# main.net
KiCad netlist of a schematic drawn in EAGLE
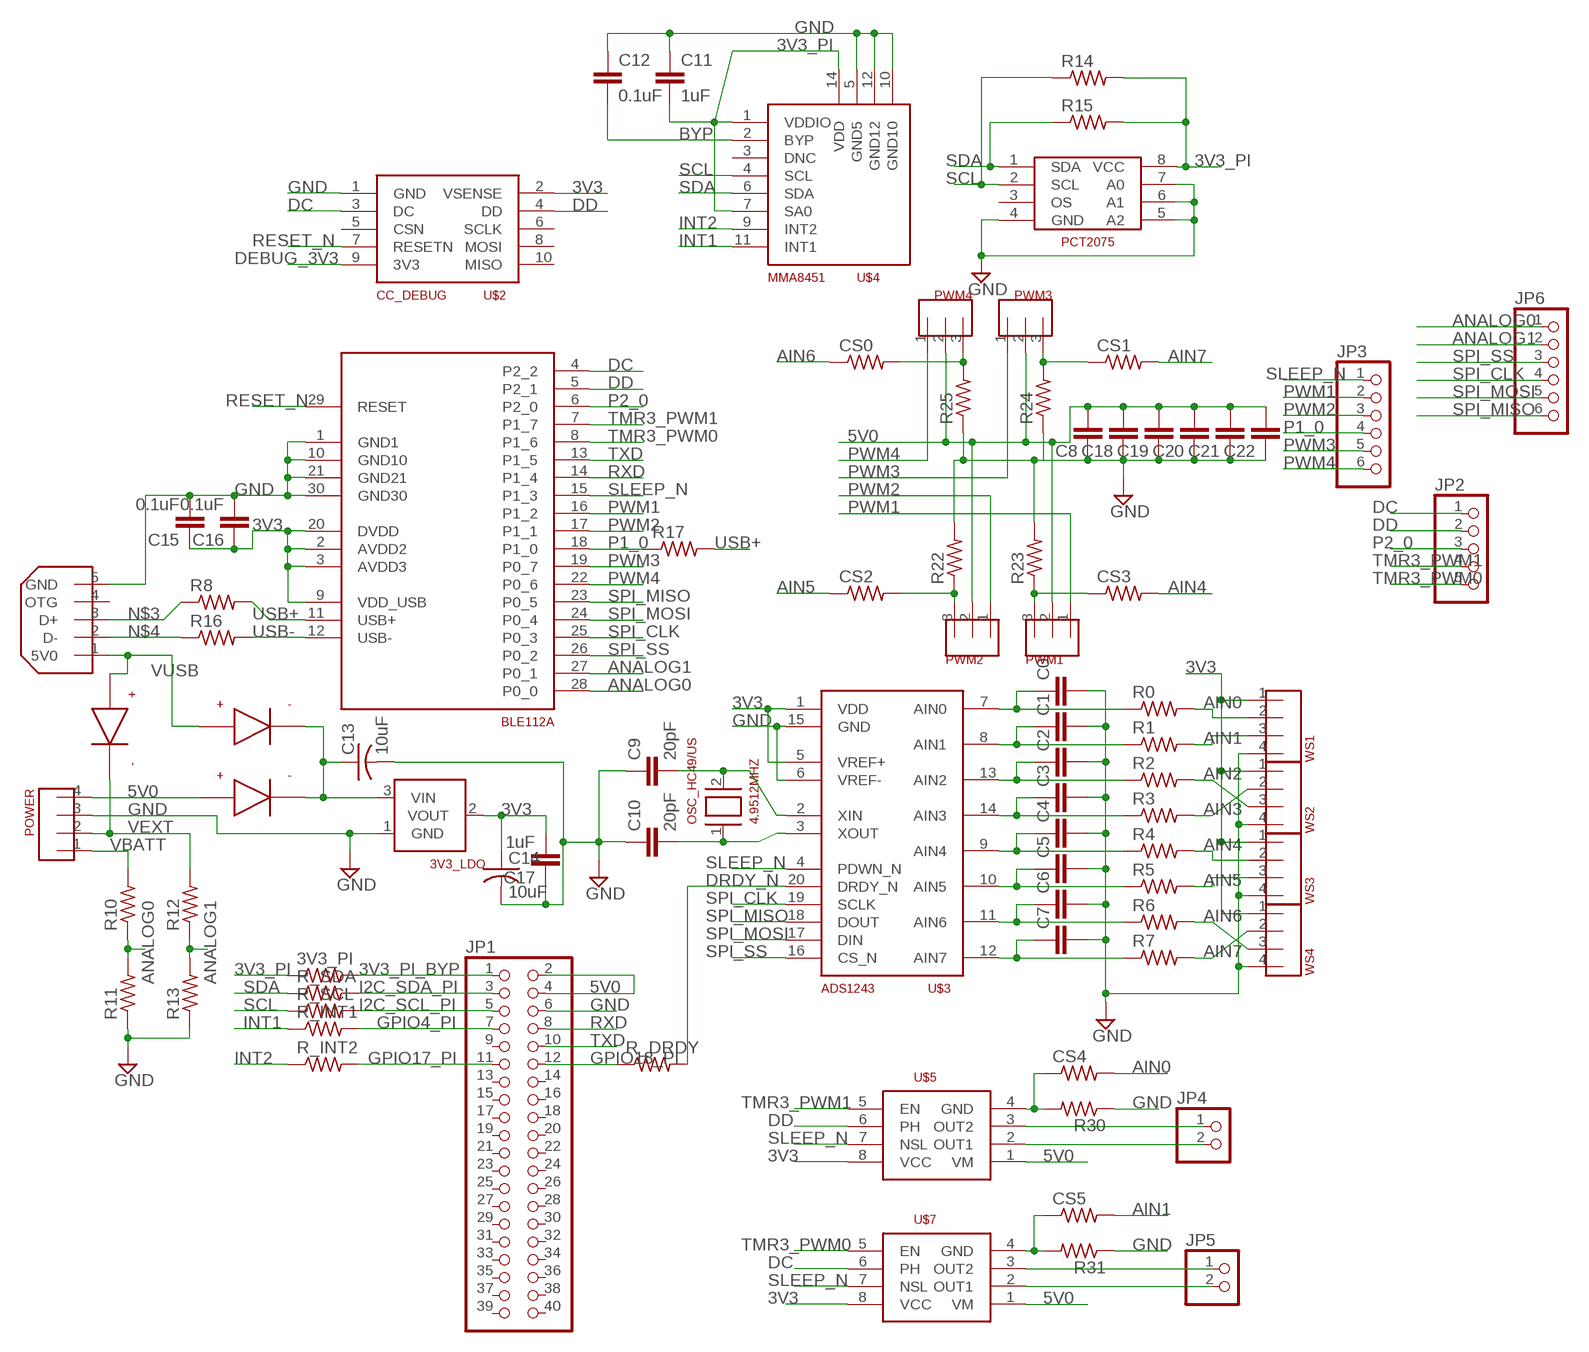
[diagram p0: schematic, sheet 1]

(export (version "E")
  (design (tool "Eeschema 10.0.6"))
  (components
    (comp (ref "3V3_LDO")
      (value "MCP1700")
      (footprint "eagle-import:SOT23")
      (libsource (lib "eagle-import") (part "MCP1700"))
    )
    (comp (ref "3V3_PI")
      (value "R-US_R0603")
      (footprint "eagle-import:R0603")
      (libsource (lib "eagle-import") (part "R-US_R0603"))
    )
    (comp (ref "4.9512MHZ")
      (value "OSC_HC49/US")
      (footprint "eagle-import:HC49UP")
      (libsource (lib "eagle-import") (part "OSC_HC49/US"))
    )
    (comp (ref "BLE112A")
      (value "BLE112A")
      (footprint "eagle-import:BLE112")
      (libsource (lib "eagle-import") (part "BLE112A"))
    )
    (comp (ref "C0")
      (value "C-EUC0603")
      (footprint "eagle-import:C0603")
      (libsource (lib "eagle-import") (part "C-EUC0603"))
    )
    (comp (ref "C1")
      (value "C-EUC0603")
      (footprint "eagle-import:C0603")
      (libsource (lib "eagle-import") (part "C-EUC0603"))
    )
    (comp (ref "C2")
      (value "C-EUC0603")
      (footprint "eagle-import:C0603")
      (libsource (lib "eagle-import") (part "C-EUC0603"))
    )
    (comp (ref "C3")
      (value "C-EUC0603")
      (footprint "eagle-import:C0603")
      (libsource (lib "eagle-import") (part "C-EUC0603"))
    )
    (comp (ref "C4")
      (value "C-EUC0603")
      (footprint "eagle-import:C0603")
      (libsource (lib "eagle-import") (part "C-EUC0603"))
    )
    (comp (ref "C5")
      (value "C-EUC0603")
      (footprint "eagle-import:C0603")
      (libsource (lib "eagle-import") (part "C-EUC0603"))
    )
    (comp (ref "C6")
      (value "C-EUC0603")
      (footprint "eagle-import:C0603")
      (libsource (lib "eagle-import") (part "C-EUC0603"))
    )
    (comp (ref "C7")
      (value "C-EUC0603")
      (footprint "eagle-import:C0603")
      (libsource (lib "eagle-import") (part "C-EUC0603"))
    )
    (comp (ref "C8")
      (value "C-EUC0603")
      (footprint "eagle-import:C0603")
      (libsource (lib "eagle-import") (part "C-EUC0603"))
    )
    (comp (ref "C9")
      (value "20pF")
      (footprint "eagle-import:C0603")
      (libsource (lib "eagle-import") (part "C-EUC0603"))
    )
    (comp (ref "C10")
      (value "20pF")
      (footprint "eagle-import:C0603")
      (libsource (lib "eagle-import") (part "C-EUC0603"))
    )
    (comp (ref "C11")
      (value "1uF")
      (footprint "eagle-import:C0603")
      (libsource (lib "eagle-import") (part "C-EUC0603"))
    )
    (comp (ref "C12")
      (value "0.1uF")
      (footprint "eagle-import:C0603")
      (libsource (lib "eagle-import") (part "C-EUC0603"))
    )
    (comp (ref "C13")
      (value "10uF")
      (footprint "eagle-import:C0805")
      (libsource (lib "eagle-import") (part "C-USC0805"))
    )
    (comp (ref "C14")
      (value "10uF")
      (footprint "eagle-import:C0805")
      (libsource (lib "eagle-import") (part "C-USC0805"))
    )
    (comp (ref "C15")
      (value "0.1uF")
      (footprint "eagle-import:C0603")
      (libsource (lib "eagle-import") (part "C-EUC0603"))
    )
    (comp (ref "C16")
      (value "0.1uF")
      (footprint "eagle-import:C0603")
      (libsource (lib "eagle-import") (part "C-EUC0603"))
    )
    (comp (ref "C17")
      (value "1uF")
      (footprint "eagle-import:C0603")
      (libsource (lib "eagle-import") (part "C-EUC0603"))
    )
    (comp (ref "C18")
      (value "C-EUC0603")
      (footprint "eagle-import:C0603")
      (libsource (lib "eagle-import") (part "C-EUC0603"))
    )
    (comp (ref "C19")
      (value "C-EUC0603")
      (footprint "eagle-import:C0603")
      (libsource (lib "eagle-import") (part "C-EUC0603"))
    )
    (comp (ref "C20")
      (value "C-EUC0603")
      (footprint "eagle-import:C0603")
      (libsource (lib "eagle-import") (part "C-EUC0603"))
    )
    (comp (ref "C21")
      (value "C-EUC0603")
      (footprint "eagle-import:C0603")
      (libsource (lib "eagle-import") (part "C-EUC0603"))
    )
    (comp (ref "C22")
      (value "C-EUC0603")
      (footprint "eagle-import:C0603")
      (libsource (lib "eagle-import") (part "C-EUC0603"))
    )
    (comp (ref "CS0")
      (value "R-US_R0603")
      (footprint "eagle-import:R0603")
      (libsource (lib "eagle-import") (part "R-US_R0603"))
    )
    (comp (ref "CS1")
      (value "R-US_R0603")
      (footprint "eagle-import:R0603")
      (libsource (lib "eagle-import") (part "R-US_R0603"))
    )
    (comp (ref "CS2")
      (value "R-US_R0603")
      (footprint "eagle-import:R0603")
      (libsource (lib "eagle-import") (part "R-US_R0603"))
    )
    (comp (ref "CS3")
      (value "R-US_R0603")
      (footprint "eagle-import:R0603")
      (libsource (lib "eagle-import") (part "R-US_R0603"))
    )
    (comp (ref "CS4")
      (value "R-US_R0603")
      (footprint "eagle-import:R0603")
      (libsource (lib "eagle-import") (part "R-US_R0603"))
    )
    (comp (ref "CS5")
      (value "R-US_R0603")
      (footprint "eagle-import:R0603")
      (libsource (lib "eagle-import") (part "R-US_R0603"))
    )
    (comp (ref "JP1")
      (value "PINHD-2X20")
      (footprint "eagle-import:2X20")
      (libsource (lib "eagle-import") (part "PINHD-2X20"))
    )
    (comp (ref "JP2")
      (value "PINHD-1X5")
      (footprint "eagle-import:1X05")
      (libsource (lib "eagle-import") (part "PINHD-1X5"))
    )
    (comp (ref "JP3")
      (value "PINHD-1X6")
      (footprint "eagle-import:1X06")
      (libsource (lib "eagle-import") (part "PINHD-1X6"))
    )
    (comp (ref "JP4")
      (value "PINHD-1X2")
      (footprint "eagle-import:1X02")
      (libsource (lib "eagle-import") (part "PINHD-1X2"))
    )
    (comp (ref "JP5")
      (value "PINHD-1X2")
      (footprint "eagle-import:1X02")
      (libsource (lib "eagle-import") (part "PINHD-1X2"))
    )
    (comp (ref "JP6")
      (value "PINHD-1X6")
      (footprint "eagle-import:1X06")
      (libsource (lib "eagle-import") (part "PINHD-1X6"))
    )
    (comp (ref "PCT2075")
      (value "PCT2075")
      (footprint "eagle-import:SO-08")
      (libsource (lib "eagle-import") (part "PCT2075"))
    )
    (comp (ref "POWER")
      (value "HDR_SPOX4")
      (footprint "eagle-import:HDR_SPOX4")
      (libsource (lib "eagle-import") (part "HDR_SPOX4"))
    )
    (comp (ref "PWM1")
      (value "HDR_1X3")
      (footprint "eagle-import:HDR_1X3")
      (libsource (lib "eagle-import") (part "HDR_1X3"))
    )
    (comp (ref "PWM2")
      (value "HDR_1X3")
      (footprint "eagle-import:HDR_1X3")
      (libsource (lib "eagle-import") (part "HDR_1X3"))
    )
    (comp (ref "PWM3")
      (value "HDR_1X3")
      (footprint "eagle-import:HDR_1X3")
      (libsource (lib "eagle-import") (part "HDR_1X3"))
    )
    (comp (ref "PWM4")
      (value "HDR_1X3")
      (footprint "eagle-import:HDR_1X3")
      (libsource (lib "eagle-import") (part "HDR_1X3"))
    )
    (comp (ref "R0")
      (value "R-US_R0603")
      (footprint "eagle-import:R0603")
      (libsource (lib "eagle-import") (part "R-US_R0603"))
    )
    (comp (ref "R1")
      (value "R-US_R0603")
      (footprint "eagle-import:R0603")
      (libsource (lib "eagle-import") (part "R-US_R0603"))
    )
    (comp (ref "R2")
      (value "R-US_R0603")
      (footprint "eagle-import:R0603")
      (libsource (lib "eagle-import") (part "R-US_R0603"))
    )
    (comp (ref "R3")
      (value "R-US_R0603")
      (footprint "eagle-import:R0603")
      (libsource (lib "eagle-import") (part "R-US_R0603"))
    )
    (comp (ref "R4")
      (value "R-US_R0603")
      (footprint "eagle-import:R0603")
      (libsource (lib "eagle-import") (part "R-US_R0603"))
    )
    (comp (ref "R5")
      (value "R-US_R0603")
      (footprint "eagle-import:R0603")
      (libsource (lib "eagle-import") (part "R-US_R0603"))
    )
    (comp (ref "R6")
      (value "R-US_R0603")
      (footprint "eagle-import:R0603")
      (libsource (lib "eagle-import") (part "R-US_R0603"))
    )
    (comp (ref "R7")
      (value "R-US_R0603")
      (footprint "eagle-import:R0603")
      (libsource (lib "eagle-import") (part "R-US_R0603"))
    )
    (comp (ref "R8")
      (value "R-US_R0603")
      (footprint "eagle-import:R0603")
      (libsource (lib "eagle-import") (part "R-US_R0603"))
    )
    (comp (ref "R10")
      (value "R-US_R0603")
      (footprint "eagle-import:R0603")
      (libsource (lib "eagle-import") (part "R-US_R0603"))
    )
    (comp (ref "R11")
      (value "R-US_R0603")
      (footprint "eagle-import:R0603")
      (libsource (lib "eagle-import") (part "R-US_R0603"))
    )
    (comp (ref "R12")
      (value "R-US_R0603")
      (footprint "eagle-import:R0603")
      (libsource (lib "eagle-import") (part "R-US_R0603"))
    )
    (comp (ref "R13")
      (value "R-US_R0603")
      (footprint "eagle-import:R0603")
      (libsource (lib "eagle-import") (part "R-US_R0603"))
    )
    (comp (ref "R14")
      (value "R-US_R0603")
      (footprint "eagle-import:R0603")
      (libsource (lib "eagle-import") (part "R-US_R0603"))
    )
    (comp (ref "R15")
      (value "R-US_R0603")
      (footprint "eagle-import:R0603")
      (libsource (lib "eagle-import") (part "R-US_R0603"))
    )
    (comp (ref "R16")
      (value "R-US_R0603")
      (footprint "eagle-import:R0603")
      (libsource (lib "eagle-import") (part "R-US_R0603"))
    )
    (comp (ref "R17")
      (value "R-US_R0603")
      (footprint "eagle-import:R0603")
      (libsource (lib "eagle-import") (part "R-US_R0603"))
    )
    (comp (ref "R22")
      (value "R-US_R1206")
      (footprint "eagle-import:R1206")
      (libsource (lib "eagle-import") (part "resistor_R-US_R1206"))
    )
    (comp (ref "R23")
      (value "R-US_R1206")
      (footprint "eagle-import:R1206")
      (libsource (lib "eagle-import") (part "resistor_R-US_R1206"))
    )
    (comp (ref "R24")
      (value "R-US_R1206")
      (footprint "eagle-import:R1206")
      (libsource (lib "eagle-import") (part "resistor_R-US_R1206"))
    )
    (comp (ref "R25")
      (value "R-US_R1206")
      (footprint "eagle-import:R1206")
      (libsource (lib "eagle-import") (part "resistor_R-US_R1206"))
    )
    (comp (ref "R30")
      (value "R-US_R1206")
      (footprint "eagle-import:R1206")
      (libsource (lib "eagle-import") (part "resistor_R-US_R1206"))
    )
    (comp (ref "R31")
      (value "R-US_R1206")
      (footprint "eagle-import:R1206")
      (libsource (lib "eagle-import") (part "resistor_R-US_R1206"))
    )
    (comp (ref "R_DRDY")
      (value "R-US_R0603")
      (footprint "eagle-import:R0603")
      (libsource (lib "eagle-import") (part "R-US_R0603"))
    )
    (comp (ref "R_INT1")
      (value "R-US_R0603")
      (footprint "eagle-import:R0603")
      (libsource (lib "eagle-import") (part "R-US_R0603"))
    )
    (comp (ref "R_INT2")
      (value "R-US_R0603")
      (footprint "eagle-import:R0603")
      (libsource (lib "eagle-import") (part "R-US_R0603"))
    )
    (comp (ref "R_SCL")
      (value "R-US_R0603")
      (footprint "eagle-import:R0603")
      (libsource (lib "eagle-import") (part "R-US_R0603"))
    )
    (comp (ref "R_SDA")
      (value "R-US_R0603")
      (footprint "eagle-import:R0603")
      (libsource (lib "eagle-import") (part "R-US_R0603"))
    )
    (comp (ref "U$1")
      (value "SCHOTTKEY_DIODE_1206")
      (footprint "eagle-import:DIODE_1206")
      (libsource (lib "eagle-import") (part "SCHOTTKEY_DIODE_1206"))
    )
    (comp (ref "U$2")
      (value "CC_DEBUG")
      (footprint "eagle-import:HDR_2X5_127MM")
      (libsource (lib "eagle-import") (part "CC_DEBUG"))
    )
    (comp (ref "U$3")
      (value "ADS1243")
      (footprint "eagle-import:TSSOP20")
      (libsource (lib "eagle-import") (part "ADS1243"))
    )
    (comp (ref "U$4")
      (value "MMA8451")
      (footprint "eagle-import:QFN16_3X3")
      (libsource (lib "eagle-import") (part "MMA8451"))
    )
    (comp (ref "U$5")
      (value "DRV8838")
      (footprint "eagle-import:WSON-8-PAD")
      (libsource (lib "eagle-import") (part "DRV8838"))
    )
    (comp (ref "U$6")
      (value "MICRO_USB")
      (footprint "eagle-import:MICRO_USB")
      (libsource (lib "eagle-import") (part "MICRO_USB"))
    )
    (comp (ref "U$7")
      (value "DRV8838")
      (footprint "eagle-import:WSON-8-PAD")
      (libsource (lib "eagle-import") (part "DRV8838"))
    )
    (comp (ref "U$11")
      (value "SCHOTTKEY_DIODE_1206")
      (footprint "eagle-import:DIODE_1206")
      (libsource (lib "eagle-import") (part "SCHOTTKEY_DIODE_1206"))
    )
    (comp (ref "U$12")
      (value "SCHOTTKEY_DIODE_1206")
      (footprint "eagle-import:DIODE_1206")
      (libsource (lib "eagle-import") (part "SCHOTTKEY_DIODE_1206"))
    )
    (comp (ref "WS1")
      (value "HDR_1X4")
      (footprint "eagle-import:HDR_1X4")
      (libsource (lib "eagle-import") (part "HDR_1X4"))
    )
    (comp (ref "WS2")
      (value "HDR_1X4")
      (footprint "eagle-import:HDR_1X4")
      (libsource (lib "eagle-import") (part "HDR_1X4"))
    )
    (comp (ref "WS3")
      (value "HDR_1X4")
      (footprint "eagle-import:HDR_1X4")
      (libsource (lib "eagle-import") (part "HDR_1X4"))
    )
    (comp (ref "WS4")
      (value "HDR_1X4")
      (footprint "eagle-import:HDR_1X4")
      (libsource (lib "eagle-import") (part "HDR_1X4"))
    )
  )
  (nets
    (net (code "1") (name "/3V3") (class "Default")
      (node (ref "3V3_LDO") (pin "2") (pinfunction "VOUT_2") (pintype "bidirectional"))
      (node (ref "BLE112A") (pin "2") (pinfunction "AVDD2_2") (pintype "bidirectional"))
      (node (ref "BLE112A") (pin "20") (pinfunction "DVDD_20") (pintype "bidirectional"))
      (node (ref "BLE112A") (pin "3") (pinfunction "AVDD3_3") (pintype "bidirectional"))
      (node (ref "BLE112A") (pin "9") (pinfunction "VDD_USB_9") (pintype "bidirectional"))
      (node (ref "C14") (pin "1") (pinfunction "1_1") (pintype "passive"))
      (node (ref "C15") (pin "1") (pinfunction "1_1") (pintype "passive"))
      (node (ref "C16") (pin "1") (pinfunction "1_1") (pintype "passive"))
      (node (ref "C17") (pin "2") (pinfunction "2_2") (pintype "passive"))
      (node (ref "U$2") (pin "2") (pinfunction "VSENSE_2") (pintype "bidirectional"))
      (node (ref "U$3") (pin "1") (pinfunction "VDD_1") (pintype "bidirectional"))
      (node (ref "U$3") (pin "5") (pinfunction "VREF+_5") (pintype "bidirectional"))
      (node (ref "U$5") (pin "8") (pinfunction "VCC_8") (pintype "bidirectional"))
      (node (ref "U$7") (pin "8") (pinfunction "VCC_8") (pintype "bidirectional"))
      (node (ref "WS1") (pin "1") (pinfunction "1_1") (pintype "bidirectional"))
      (node (ref "WS2") (pin "1") (pinfunction "1_1") (pintype "bidirectional"))
      (node (ref "WS3") (pin "1") (pinfunction "1_1") (pintype "bidirectional"))
      (node (ref "WS4") (pin "1") (pinfunction "1_1") (pintype "bidirectional"))
    )
    (net (code "2") (name "/3V3_PI") (class "Default")
      (node (ref "3V3_PI") (pin "1") (pinfunction "1_1") (pintype "passive"))
      (node (ref "C11") (pin "2") (pinfunction "2_2") (pintype "passive"))
      (node (ref "PCT2075") (pin "8") (pinfunction "VCC_8") (pintype "bidirectional"))
      (node (ref "R14") (pin "2") (pinfunction "2_2") (pintype "passive"))
      (node (ref "R15") (pin "2") (pinfunction "2_2") (pintype "passive"))
      (node (ref "U$4") (pin "1") (pinfunction "VDDIO_1") (pintype "bidirectional"))
      (node (ref "U$4") (pin "14") (pinfunction "VDD_14") (pintype "bidirectional"))
      (node (ref "U$4") (pin "7") (pinfunction "SA0_7") (pintype "bidirectional"))
    )
    (net (code "3") (name "/3V3_PI_BYP") (class "Default")
      (node (ref "3V3_PI") (pin "2") (pinfunction "2_2") (pintype "passive"))
      (node (ref "JP1") (pin "1") (pinfunction "1_1") (pintype "passive"))
    )
    (net (code "4") (name "/5V0") (class "Default")
      (node (ref "C18") (pin "2") (pinfunction "2_2") (pintype "passive"))
      (node (ref "C19") (pin "2") (pinfunction "2_2") (pintype "passive"))
      (node (ref "C20") (pin "2") (pinfunction "2_2") (pintype "passive"))
      (node (ref "C21") (pin "2") (pinfunction "2_2") (pintype "passive"))
      (node (ref "C22") (pin "2") (pinfunction "2_2") (pintype "passive"))
      (node (ref "C8") (pin "2") (pinfunction "2_2") (pintype "passive"))
      (node (ref "JP1") (pin "2") (pinfunction "2_2") (pintype "passive"))
      (node (ref "JP1") (pin "4") (pinfunction "4_4") (pintype "passive"))
      (node (ref "POWER") (pin "4") (pinfunction "4_4") (pintype "bidirectional"))
      (node (ref "PWM1") (pin "2") (pinfunction "2_2") (pintype "bidirectional"))
      (node (ref "PWM2") (pin "2") (pinfunction "2_2") (pintype "bidirectional"))
      (node (ref "PWM3") (pin "2") (pinfunction "2_2") (pintype "bidirectional"))
      (node (ref "PWM4") (pin "2") (pinfunction "2_2") (pintype "bidirectional"))
      (node (ref "U$12") (pin "CATHODE+") (pinfunction "CATHODE+_CATHODE+") (pintype "bidirectional"))
      (node (ref "U$5") (pin "1") (pinfunction "VM_1") (pintype "bidirectional"))
      (node (ref "U$7") (pin "1") (pinfunction "VM_1") (pintype "bidirectional"))
    )
    (net (code "5") (name "/AIN0") (class "Default")
      (node (ref "CS4") (pin "2") (pinfunction "2_2") (pintype "passive"))
      (node (ref "R0") (pin "2") (pinfunction "2_2") (pintype "passive"))
      (node (ref "WS1") (pin "2") (pinfunction "2_2") (pintype "bidirectional"))
    )
    (net (code "6") (name "/AIN1") (class "Default")
      (node (ref "CS5") (pin "2") (pinfunction "2_2") (pintype "passive"))
      (node (ref "R1") (pin "2") (pinfunction "2_2") (pintype "passive"))
      (node (ref "WS1") (pin "3") (pinfunction "3_3") (pintype "bidirectional"))
    )
    (net (code "7") (name "/AIN2") (class "Default")
      (node (ref "R2") (pin "2") (pinfunction "2_2") (pintype "passive"))
      (node (ref "WS2") (pin "3") (pinfunction "3_3") (pintype "bidirectional"))
    )
    (net (code "8") (name "/AIN3") (class "Default")
      (node (ref "R3") (pin "2") (pinfunction "2_2") (pintype "passive"))
      (node (ref "WS2") (pin "2") (pinfunction "2_2") (pintype "bidirectional"))
    )
    (net (code "9") (name "/AIN4") (class "Default")
      (node (ref "CS3") (pin "2") (pinfunction "2_2") (pintype "passive"))
      (node (ref "R4") (pin "2") (pinfunction "2_2") (pintype "passive"))
      (node (ref "WS3") (pin "2") (pinfunction "2_2") (pintype "bidirectional"))
    )
    (net (code "10") (name "/AIN5") (class "Default")
      (node (ref "CS2") (pin "1") (pinfunction "1_1") (pintype "passive"))
      (node (ref "R5") (pin "2") (pinfunction "2_2") (pintype "passive"))
      (node (ref "WS3") (pin "3") (pinfunction "3_3") (pintype "bidirectional"))
    )
    (net (code "11") (name "/AIN6") (class "Default")
      (node (ref "CS0") (pin "1") (pinfunction "1_1") (pintype "passive"))
      (node (ref "R6") (pin "2") (pinfunction "2_2") (pintype "passive"))
      (node (ref "WS4") (pin "3") (pinfunction "3_3") (pintype "bidirectional"))
    )
    (net (code "12") (name "/AIN7") (class "Default")
      (node (ref "CS1") (pin "2") (pinfunction "2_2") (pintype "passive"))
      (node (ref "R7") (pin "2") (pinfunction "2_2") (pintype "passive"))
      (node (ref "WS4") (pin "2") (pinfunction "2_2") (pintype "bidirectional"))
    )
    (net (code "13") (name "/ANALOG0") (class "Default")
      (node (ref "BLE112A") (pin "28") (pinfunction "P0_0_28") (pintype "bidirectional"))
      (node (ref "JP6") (pin "1") (pinfunction "1_1") (pintype "passive"))
      (node (ref "R10") (pin "1") (pinfunction "1_1") (pintype "passive"))
      (node (ref "R11") (pin "2") (pinfunction "2_2") (pintype "passive"))
    )
    (net (code "14") (name "/ANALOG1") (class "Default")
      (node (ref "BLE112A") (pin "27") (pinfunction "P0_1_27") (pintype "bidirectional"))
      (node (ref "JP6") (pin "2") (pinfunction "2_2") (pintype "passive"))
      (node (ref "R12") (pin "1") (pinfunction "1_1") (pintype "passive"))
      (node (ref "R13") (pin "2") (pinfunction "2_2") (pintype "passive"))
    )
    (net (code "15") (name "/BYP") (class "Default")
      (node (ref "C12") (pin "2") (pinfunction "2_2") (pintype "passive"))
      (node (ref "U$4") (pin "2") (pinfunction "BYP_2") (pintype "bidirectional"))
    )
    (net (code "16") (name "/DC") (class "Default")
      (node (ref "BLE112A") (pin "4") (pinfunction "P2_2_4") (pintype "bidirectional"))
      (node (ref "JP2") (pin "1") (pinfunction "1_1") (pintype "passive"))
      (node (ref "U$2") (pin "3") (pinfunction "DC_3") (pintype "bidirectional"))
      (node (ref "U$7") (pin "6") (pinfunction "PH_6") (pintype "bidirectional"))
    )
    (net (code "17") (name "/DD") (class "Default")
      (node (ref "BLE112A") (pin "5") (pinfunction "P2_1_5") (pintype "bidirectional"))
      (node (ref "JP2") (pin "2") (pinfunction "2_2") (pintype "passive"))
      (node (ref "U$2") (pin "4") (pinfunction "DD_4") (pintype "bidirectional"))
      (node (ref "U$5") (pin "6") (pinfunction "PH_6") (pintype "bidirectional"))
    )
    (net (code "18") (name "/DEBUG_3V3") (class "Default")
      (node (ref "U$2") (pin "9") (pinfunction "3V3_9") (pintype "bidirectional"))
    )
    (net (code "19") (name "/DRDY_N") (class "Default")
      (node (ref "R_DRDY") (pin "2") (pinfunction "2_2") (pintype "passive"))
      (node (ref "U$3") (pin "20") (pinfunction "DRDY_N_20") (pintype "bidirectional"))
    )
    (net (code "20") (name "/GPIO4_PI") (class "Default")
      (node (ref "JP1") (pin "7") (pinfunction "7_7") (pintype "passive"))
      (node (ref "R_INT1") (pin "2") (pinfunction "2_2") (pintype "passive"))
    )
    (net (code "21") (name "/GPIO17_PI") (class "Default")
      (node (ref "JP1") (pin "11") (pinfunction "11_11") (pintype "passive"))
      (node (ref "R_INT2") (pin "2") (pinfunction "2_2") (pintype "passive"))
    )
    (net (code "22") (name "/GPIO18_PI") (class "Default")
      (node (ref "JP1") (pin "12") (pinfunction "12_12") (pintype "passive"))
      (node (ref "R_DRDY") (pin "1") (pinfunction "1_1") (pintype "passive"))
    )
    (net (code "23") (name "/I2C_SCL_PI") (class "Default")
      (node (ref "JP1") (pin "5") (pinfunction "5_5") (pintype "passive"))
      (node (ref "R_SCL") (pin "2") (pinfunction "2_2") (pintype "passive"))
    )
    (net (code "24") (name "/I2C_SDA_PI") (class "Default")
      (node (ref "JP1") (pin "3") (pinfunction "3_3") (pintype "passive"))
      (node (ref "R_SDA") (pin "2") (pinfunction "2_2") (pintype "passive"))
    )
    (net (code "25") (name "/INT1") (class "Default")
      (node (ref "R_INT1") (pin "1") (pinfunction "1_1") (pintype "passive"))
      (node (ref "U$4") (pin "11") (pinfunction "INT1_11") (pintype "bidirectional"))
    )
    (net (code "26") (name "/INT2") (class "Default")
      (node (ref "R_INT2") (pin "1") (pinfunction "1_1") (pintype "passive"))
      (node (ref "U$4") (pin "9") (pinfunction "INT2_9") (pintype "bidirectional"))
    )
    (net (code "27") (name "/N$3") (class "Default")
      (node (ref "R8") (pin "1") (pinfunction "1_1") (pintype "passive"))
      (node (ref "U$6") (pin "3") (pinfunction "D+_3") (pintype "bidirectional"))
    )
    (net (code "28") (name "/N$4") (class "Default")
      (node (ref "R16") (pin "1") (pinfunction "1_1") (pintype "passive"))
      (node (ref "U$6") (pin "2") (pinfunction "D-_2") (pintype "bidirectional"))
    )
    (net (code "29") (name "/P1_0") (class "Default")
      (node (ref "BLE112A") (pin "18") (pinfunction "P1_0_18") (pintype "bidirectional"))
      (node (ref "JP3") (pin "4") (pinfunction "4_4") (pintype "passive"))
      (node (ref "R17") (pin "1") (pinfunction "1_1") (pintype "passive"))
    )
    (net (code "30") (name "/P2_0") (class "Default")
      (node (ref "BLE112A") (pin "6") (pinfunction "P2_0_6") (pintype "bidirectional"))
      (node (ref "JP2") (pin "3") (pinfunction "3_3") (pintype "passive"))
    )
    (net (code "31") (name "/PWM1") (class "Default")
      (node (ref "BLE112A") (pin "16") (pinfunction "P1_2_16") (pintype "bidirectional"))
      (node (ref "JP3") (pin "2") (pinfunction "2_2") (pintype "passive"))
      (node (ref "PWM1") (pin "1") (pinfunction "1_1") (pintype "bidirectional"))
    )
    (net (code "32") (name "/PWM2") (class "Default")
      (node (ref "BLE112A") (pin "17") (pinfunction "P1_1_17") (pintype "bidirectional"))
      (node (ref "JP3") (pin "3") (pinfunction "3_3") (pintype "passive"))
      (node (ref "PWM2") (pin "1") (pinfunction "1_1") (pintype "bidirectional"))
    )
    (net (code "33") (name "/PWM3") (class "Default")
      (node (ref "BLE112A") (pin "19") (pinfunction "P0_7_19") (pintype "bidirectional"))
      (node (ref "JP3") (pin "5") (pinfunction "5_5") (pintype "passive"))
      (node (ref "PWM3") (pin "1") (pinfunction "1_1") (pintype "bidirectional"))
    )
    (net (code "34") (name "/PWM4") (class "Default")
      (node (ref "BLE112A") (pin "22") (pinfunction "P0_6_22") (pintype "bidirectional"))
      (node (ref "JP3") (pin "6") (pinfunction "6_6") (pintype "passive"))
      (node (ref "PWM4") (pin "1") (pinfunction "1_1") (pintype "bidirectional"))
    )
    (net (code "35") (name "/RESET_N") (class "Default")
      (node (ref "BLE112A") (pin "29") (pinfunction "RESET_29") (pintype "bidirectional"))
      (node (ref "U$2") (pin "7") (pinfunction "RESETN_7") (pintype "bidirectional"))
    )
    (net (code "36") (name "/RXD") (class "Default")
      (node (ref "BLE112A") (pin "14") (pinfunction "P1_4_14") (pintype "bidirectional"))
      (node (ref "JP1") (pin "8") (pinfunction "8_8") (pintype "passive"))
    )
    (net (code "37") (name "/SCL") (class "Default")
      (node (ref "PCT2075") (pin "2") (pinfunction "SCL_2") (pintype "bidirectional"))
      (node (ref "R14") (pin "1") (pinfunction "1_1") (pintype "passive"))
      (node (ref "R_SCL") (pin "1") (pinfunction "1_1") (pintype "passive"))
      (node (ref "U$4") (pin "4") (pinfunction "SCL_4") (pintype "bidirectional"))
    )
    (net (code "38") (name "/SDA") (class "Default")
      (node (ref "PCT2075") (pin "1") (pinfunction "SDA_1") (pintype "bidirectional"))
      (node (ref "R15") (pin "1") (pinfunction "1_1") (pintype "passive"))
      (node (ref "R_SDA") (pin "1") (pinfunction "1_1") (pintype "passive"))
      (node (ref "U$4") (pin "6") (pinfunction "SDA_6") (pintype "bidirectional"))
    )
    (net (code "39") (name "/SLEEP_N") (class "Default")
      (node (ref "BLE112A") (pin "15") (pinfunction "P1_3_15") (pintype "bidirectional"))
      (node (ref "JP3") (pin "1") (pinfunction "1_1") (pintype "passive"))
      (node (ref "U$3") (pin "4") (pinfunction "PDWN_N_4") (pintype "bidirectional"))
      (node (ref "U$5") (pin "7") (pinfunction "NSL_7") (pintype "bidirectional"))
      (node (ref "U$7") (pin "7") (pinfunction "NSL_7") (pintype "bidirectional"))
    )
    (net (code "40") (name "/SPI_CLK") (class "Default")
      (node (ref "BLE112A") (pin "25") (pinfunction "P0_3_25") (pintype "bidirectional"))
      (node (ref "JP6") (pin "4") (pinfunction "4_4") (pintype "passive"))
      (node (ref "U$3") (pin "19") (pinfunction "SCLK_19") (pintype "bidirectional"))
    )
    (net (code "41") (name "/SPI_MISO") (class "Default")
      (node (ref "BLE112A") (pin "23") (pinfunction "P0_5_23") (pintype "bidirectional"))
      (node (ref "JP6") (pin "6") (pinfunction "6_6") (pintype "passive"))
      (node (ref "U$3") (pin "18") (pinfunction "DOUT_18") (pintype "bidirectional"))
    )
    (net (code "42") (name "/SPI_MOSI") (class "Default")
      (node (ref "BLE112A") (pin "24") (pinfunction "P0_4_24") (pintype "bidirectional"))
      (node (ref "JP6") (pin "5") (pinfunction "5_5") (pintype "passive"))
      (node (ref "U$3") (pin "17") (pinfunction "DIN_17") (pintype "bidirectional"))
    )
    (net (code "43") (name "/SPI_SS") (class "Default")
      (node (ref "BLE112A") (pin "26") (pinfunction "P0_2_26") (pintype "bidirectional"))
      (node (ref "JP6") (pin "3") (pinfunction "3_3") (pintype "passive"))
      (node (ref "U$3") (pin "16") (pinfunction "CS_N_16") (pintype "bidirectional"))
    )
    (net (code "44") (name "/TMR3_PWM0") (class "Default")
      (node (ref "BLE112A") (pin "8") (pinfunction "P1_6_8") (pintype "bidirectional"))
      (node (ref "JP2") (pin "5") (pinfunction "5_5") (pintype "passive"))
      (node (ref "U$7") (pin "5") (pinfunction "EN_5") (pintype "bidirectional"))
    )
    (net (code "45") (name "/TMR3_PWM1") (class "Default")
      (node (ref "BLE112A") (pin "7") (pinfunction "P1_7_7") (pintype "bidirectional"))
      (node (ref "JP2") (pin "4") (pinfunction "4_4") (pintype "passive"))
      (node (ref "U$5") (pin "5") (pinfunction "EN_5") (pintype "bidirectional"))
    )
    (net (code "46") (name "/TXD") (class "Default")
      (node (ref "BLE112A") (pin "13") (pinfunction "P1_5_13") (pintype "bidirectional"))
      (node (ref "JP1") (pin "10") (pinfunction "10_10") (pintype "passive"))
    )
    (net (code "47") (name "/USB+") (class "Default")
      (node (ref "BLE112A") (pin "11") (pinfunction "USB+_11") (pintype "bidirectional"))
      (node (ref "R17") (pin "2") (pinfunction "2_2") (pintype "passive"))
      (node (ref "R8") (pin "2") (pinfunction "2_2") (pintype "passive"))
    )
    (net (code "48") (name "/USB-") (class "Default")
      (node (ref "BLE112A") (pin "12") (pinfunction "USB-_12") (pintype "bidirectional"))
      (node (ref "R16") (pin "2") (pinfunction "2_2") (pintype "passive"))
    )
    (net (code "49") (name "/VBATT") (class "Default")
      (node (ref "POWER") (pin "1") (pinfunction "1_1") (pintype "bidirectional"))
      (node (ref "R10") (pin "2") (pinfunction "2_2") (pintype "passive"))
    )
    (net (code "50") (name "/VEXT") (class "Default")
      (node (ref "POWER") (pin "2") (pinfunction "2_2") (pintype "bidirectional"))
      (node (ref "R12") (pin "2") (pinfunction "2_2") (pintype "passive"))
      (node (ref "U$1") (pin "ANODE-") (pinfunction "ANODE-_ANODE-") (pintype "bidirectional"))
    )
    (net (code "51") (name "/VUSB") (class "Default")
      (node (ref "U$1") (pin "CATHODE+") (pinfunction "CATHODE+_CATHODE+") (pintype "bidirectional"))
      (node (ref "U$11") (pin "CATHODE+") (pinfunction "CATHODE+_CATHODE+") (pintype "bidirectional"))
      (node (ref "U$6") (pin "1") (pinfunction "5V0_1") (pintype "bidirectional"))
    )
    (net (code "52") (name "GND") (class "Default")
      (node (ref "3V3_LDO") (pin "1") (pinfunction "GND_1") (pintype "bidirectional"))
      (node (ref "BLE112A") (pin "1") (pinfunction "GND1_1") (pintype "bidirectional"))
      (node (ref "BLE112A") (pin "10") (pinfunction "GND10_10") (pintype "bidirectional"))
      (node (ref "BLE112A") (pin "21") (pinfunction "GND21_21") (pintype "bidirectional"))
      (node (ref "BLE112A") (pin "30") (pinfunction "GND30_30") (pintype "bidirectional"))
      (node (ref "C0") (pin "2") (pinfunction "2_2") (pintype "passive"))
      (node (ref "C1") (pin "2") (pinfunction "2_2") (pintype "passive"))
      (node (ref "C10") (pin "1") (pinfunction "1_1") (pintype "passive"))
      (node (ref "C11") (pin "1") (pinfunction "1_1") (pintype "passive"))
      (node (ref "C12") (pin "1") (pinfunction "1_1") (pintype "passive"))
      (node (ref "C13") (pin "2") (pinfunction "2_2") (pintype "passive"))
      (node (ref "C14") (pin "2") (pinfunction "2_2") (pintype "passive"))
      (node (ref "C15") (pin "2") (pinfunction "2_2") (pintype "passive"))
      (node (ref "C16") (pin "2") (pinfunction "2_2") (pintype "passive"))
      (node (ref "C17") (pin "1") (pinfunction "1_1") (pintype "passive"))
      (node (ref "C18") (pin "1") (pinfunction "1_1") (pintype "passive"))
      (node (ref "C19") (pin "1") (pinfunction "1_1") (pintype "passive"))
      (node (ref "C2") (pin "2") (pinfunction "2_2") (pintype "passive"))
      (node (ref "C20") (pin "1") (pinfunction "1_1") (pintype "passive"))
      (node (ref "C21") (pin "1") (pinfunction "1_1") (pintype "passive"))
      (node (ref "C22") (pin "1") (pinfunction "1_1") (pintype "passive"))
      (node (ref "C3") (pin "2") (pinfunction "2_2") (pintype "passive"))
      (node (ref "C4") (pin "2") (pinfunction "2_2") (pintype "passive"))
      (node (ref "C5") (pin "2") (pinfunction "2_2") (pintype "passive"))
      (node (ref "C6") (pin "2") (pinfunction "2_2") (pintype "passive"))
      (node (ref "C7") (pin "2") (pinfunction "2_2") (pintype "passive"))
      (node (ref "C8") (pin "1") (pinfunction "1_1") (pintype "passive"))
      (node (ref "C9") (pin "1") (pinfunction "1_1") (pintype "passive"))
      (node (ref "JP1") (pin "6") (pinfunction "6_6") (pintype "passive"))
      (node (ref "PCT2075") (pin "4") (pinfunction "GND_4") (pintype "bidirectional"))
      (node (ref "PCT2075") (pin "5") (pinfunction "A2_5") (pintype "bidirectional"))
      (node (ref "PCT2075") (pin "6") (pinfunction "A1_6") (pintype "bidirectional"))
      (node (ref "PCT2075") (pin "7") (pinfunction "A0_7") (pintype "bidirectional"))
      (node (ref "POWER") (pin "3") (pinfunction "3_3") (pintype "bidirectional"))
      (node (ref "R11") (pin "1") (pinfunction "1_1") (pintype "passive"))
      (node (ref "R13") (pin "1") (pinfunction "1_1") (pintype "passive"))
      (node (ref "R22") (pin "2") (pinfunction "2_2") (pintype "passive"))
      (node (ref "R23") (pin "2") (pinfunction "2_2") (pintype "passive"))
      (node (ref "R24") (pin "1") (pinfunction "1_1") (pintype "passive"))
      (node (ref "R25") (pin "1") (pinfunction "1_1") (pintype "passive"))
      (node (ref "R30") (pin "1") (pinfunction "1_1") (pintype "passive"))
      (node (ref "R31") (pin "1") (pinfunction "1_1") (pintype "passive"))
      (node (ref "U$2") (pin "1") (pinfunction "GND_1") (pintype "bidirectional"))
      (node (ref "U$3") (pin "15") (pinfunction "GND_15") (pintype "bidirectional"))
      (node (ref "U$3") (pin "6") (pinfunction "VREF-_6") (pintype "bidirectional"))
      (node (ref "U$4") (pin "10") (pinfunction "GND10_10") (pintype "bidirectional"))
      (node (ref "U$4") (pin "12") (pinfunction "GND12_12") (pintype "bidirectional"))
      (node (ref "U$4") (pin "5") (pinfunction "GND5_5") (pintype "bidirectional"))
      (node (ref "U$6") (pin "5") (pinfunction "GND_5") (pintype "bidirectional"))
      (node (ref "WS1") (pin "4") (pinfunction "4_4") (pintype "bidirectional"))
      (node (ref "WS2") (pin "4") (pinfunction "4_4") (pintype "bidirectional"))
      (node (ref "WS3") (pin "4") (pinfunction "4_4") (pintype "bidirectional"))
      (node (ref "WS4") (pin "4") (pinfunction "4_4") (pintype "bidirectional"))
    )
    (net (code "53") (name "Net-(3V3_LDO-VIN)") (class "Default")
      (node (ref "3V3_LDO") (pin "3") (pinfunction "VIN_3") (pintype "bidirectional"))
      (node (ref "C13") (pin "1") (pinfunction "1_1") (pintype "passive"))
      (node (ref "U$11") (pin "ANODE-") (pinfunction "ANODE-_ANODE-") (pintype "bidirectional"))
      (node (ref "U$12") (pin "ANODE-") (pinfunction "ANODE-_ANODE-") (pintype "bidirectional"))
    )
    (net (code "54") (name "Net-(CS0-Pad2)") (class "Default")
      (node (ref "CS0") (pin "2") (pinfunction "2_2") (pintype "passive"))
      (node (ref "PWM4") (pin "3") (pinfunction "3_3") (pintype "bidirectional"))
      (node (ref "R25") (pin "2") (pinfunction "2_2") (pintype "passive"))
    )
    (net (code "55") (name "Net-(CS1-Pad1)") (class "Default")
      (node (ref "CS1") (pin "1") (pinfunction "1_1") (pintype "passive"))
      (node (ref "PWM3") (pin "3") (pinfunction "3_3") (pintype "bidirectional"))
      (node (ref "R24") (pin "2") (pinfunction "2_2") (pintype "passive"))
    )
    (net (code "56") (name "Net-(CS2-Pad2)") (class "Default")
      (node (ref "CS2") (pin "2") (pinfunction "2_2") (pintype "passive"))
      (node (ref "PWM2") (pin "3") (pinfunction "3_3") (pintype "bidirectional"))
      (node (ref "R22") (pin "1") (pinfunction "1_1") (pintype "passive"))
    )
    (net (code "57") (name "Net-(CS3-Pad1)") (class "Default")
      (node (ref "CS3") (pin "1") (pinfunction "1_1") (pintype "passive"))
      (node (ref "PWM1") (pin "3") (pinfunction "3_3") (pintype "bidirectional"))
      (node (ref "R23") (pin "1") (pinfunction "1_1") (pintype "passive"))
    )
    (net (code "58") (name "Net-(U$3-AIN0)") (class "Default")
      (node (ref "C0") (pin "1") (pinfunction "1_1") (pintype "passive"))
      (node (ref "R0") (pin "1") (pinfunction "1_1") (pintype "passive"))
      (node (ref "U$3") (pin "7") (pinfunction "AIN0_7") (pintype "bidirectional"))
    )
    (net (code "59") (name "Net-(U$3-AIN1)") (class "Default")
      (node (ref "C1") (pin "1") (pinfunction "1_1") (pintype "passive"))
      (node (ref "R1") (pin "1") (pinfunction "1_1") (pintype "passive"))
      (node (ref "U$3") (pin "8") (pinfunction "AIN1_8") (pintype "bidirectional"))
    )
    (net (code "60") (name "Net-(U$3-AIN2)") (class "Default")
      (node (ref "C2") (pin "1") (pinfunction "1_1") (pintype "passive"))
      (node (ref "R2") (pin "1") (pinfunction "1_1") (pintype "passive"))
      (node (ref "U$3") (pin "13") (pinfunction "AIN2_13") (pintype "bidirectional"))
    )
    (net (code "61") (name "Net-(U$3-AIN3)") (class "Default")
      (node (ref "C3") (pin "1") (pinfunction "1_1") (pintype "passive"))
      (node (ref "R3") (pin "1") (pinfunction "1_1") (pintype "passive"))
      (node (ref "U$3") (pin "14") (pinfunction "AIN3_14") (pintype "bidirectional"))
    )
    (net (code "62") (name "Net-(U$3-AIN4)") (class "Default")
      (node (ref "C4") (pin "1") (pinfunction "1_1") (pintype "passive"))
      (node (ref "R4") (pin "1") (pinfunction "1_1") (pintype "passive"))
      (node (ref "U$3") (pin "9") (pinfunction "AIN4_9") (pintype "bidirectional"))
    )
    (net (code "63") (name "Net-(U$3-AIN5)") (class "Default")
      (node (ref "C5") (pin "1") (pinfunction "1_1") (pintype "passive"))
      (node (ref "R5") (pin "1") (pinfunction "1_1") (pintype "passive"))
      (node (ref "U$3") (pin "10") (pinfunction "AIN5_10") (pintype "bidirectional"))
    )
    (net (code "64") (name "Net-(U$3-AIN6)") (class "Default")
      (node (ref "C6") (pin "1") (pinfunction "1_1") (pintype "passive"))
      (node (ref "R6") (pin "1") (pinfunction "1_1") (pintype "passive"))
      (node (ref "U$3") (pin "11") (pinfunction "AIN6_11") (pintype "bidirectional"))
    )
    (net (code "65") (name "Net-(U$3-AIN7)") (class "Default")
      (node (ref "C7") (pin "1") (pinfunction "1_1") (pintype "passive"))
      (node (ref "R7") (pin "1") (pinfunction "1_1") (pintype "passive"))
      (node (ref "U$3") (pin "12") (pinfunction "AIN7_12") (pintype "bidirectional"))
    )
    (net (code "66") (name "Net-(U$3-XIN)") (class "Default")
      (node (ref "4.9512MHZ") (pin "2") (pinfunction "2_2") (pintype "bidirectional"))
      (node (ref "C9") (pin "2") (pinfunction "2_2") (pintype "passive"))
      (node (ref "U$3") (pin "2") (pinfunction "XIN_2") (pintype "bidirectional"))
    )
    (net (code "67") (name "Net-(U$3-XOUT)") (class "Default")
      (node (ref "4.9512MHZ") (pin "1") (pinfunction "1_1") (pintype "bidirectional"))
      (node (ref "C10") (pin "2") (pinfunction "2_2") (pintype "passive"))
      (node (ref "U$3") (pin "3") (pinfunction "XOUT_3") (pintype "bidirectional"))
    )
    (net (code "68") (name "Net-(U$5-GND)") (class "Default")
      (node (ref "CS4") (pin "1") (pinfunction "1_1") (pintype "passive"))
      (node (ref "R30") (pin "2") (pinfunction "2_2") (pintype "passive"))
      (node (ref "U$5") (pin "4") (pinfunction "GND_4") (pintype "bidirectional"))
    )
    (net (code "69") (name "Net-(U$5-OUT1)") (class "Default")
      (node (ref "JP4") (pin "2") (pinfunction "2_2") (pintype "passive"))
      (node (ref "U$5") (pin "2") (pinfunction "OUT1_2") (pintype "bidirectional"))
    )
    (net (code "70") (name "Net-(U$5-OUT2)") (class "Default")
      (node (ref "JP4") (pin "1") (pinfunction "1_1") (pintype "passive"))
      (node (ref "U$5") (pin "3") (pinfunction "OUT2_3") (pintype "bidirectional"))
    )
    (net (code "71") (name "Net-(U$7-GND)") (class "Default")
      (node (ref "CS5") (pin "1") (pinfunction "1_1") (pintype "passive"))
      (node (ref "R31") (pin "2") (pinfunction "2_2") (pintype "passive"))
      (node (ref "U$7") (pin "4") (pinfunction "GND_4") (pintype "bidirectional"))
    )
    (net (code "72") (name "Net-(U$7-OUT1)") (class "Default")
      (node (ref "JP5") (pin "2") (pinfunction "2_2") (pintype "passive"))
      (node (ref "U$7") (pin "2") (pinfunction "OUT1_2") (pintype "bidirectional"))
    )
    (net (code "73") (name "Net-(U$7-OUT2)") (class "Default")
      (node (ref "JP5") (pin "1") (pinfunction "1_1") (pintype "passive"))
      (node (ref "U$7") (pin "3") (pinfunction "OUT2_3") (pintype "bidirectional"))
    )
    (net (code "74") (name "unconnected-(JP1-Pad9)") (class "Default")
      (node (ref "JP1") (pin "9") (pinfunction "9_9") (pintype "passive"))
    )
    (net (code "75") (name "unconnected-(JP1-Pad13)") (class "Default")
      (node (ref "JP1") (pin "13") (pinfunction "13_13") (pintype "passive"))
    )
    (net (code "76") (name "unconnected-(JP1-Pad14)") (class "Default")
      (node (ref "JP1") (pin "14") (pinfunction "14_14") (pintype "passive"))
    )
    (net (code "77") (name "unconnected-(JP1-Pad15)") (class "Default")
      (node (ref "JP1") (pin "15") (pinfunction "15_15") (pintype "passive"))
    )
    (net (code "78") (name "unconnected-(JP1-Pad16)") (class "Default")
      (node (ref "JP1") (pin "16") (pinfunction "16_16") (pintype "passive"))
    )
    (net (code "79") (name "unconnected-(JP1-Pad17)") (class "Default")
      (node (ref "JP1") (pin "17") (pinfunction "17_17") (pintype "passive"))
    )
    (net (code "80") (name "unconnected-(JP1-Pad18)") (class "Default")
      (node (ref "JP1") (pin "18") (pinfunction "18_18") (pintype "passive"))
    )
    (net (code "81") (name "unconnected-(JP1-Pad19)") (class "Default")
      (node (ref "JP1") (pin "19") (pinfunction "19_19") (pintype "passive"))
    )
    (net (code "82") (name "unconnected-(JP1-Pad20)") (class "Default")
      (node (ref "JP1") (pin "20") (pinfunction "20_20") (pintype "passive"))
    )
    (net (code "83") (name "unconnected-(JP1-Pad21)") (class "Default")
      (node (ref "JP1") (pin "21") (pinfunction "21_21") (pintype "passive"))
    )
    (net (code "84") (name "unconnected-(JP1-Pad22)") (class "Default")
      (node (ref "JP1") (pin "22") (pinfunction "22_22") (pintype "passive"))
    )
    (net (code "85") (name "unconnected-(JP1-Pad23)") (class "Default")
      (node (ref "JP1") (pin "23") (pinfunction "23_23") (pintype "passive"))
    )
    (net (code "86") (name "unconnected-(JP1-Pad24)") (class "Default")
      (node (ref "JP1") (pin "24") (pinfunction "24_24") (pintype "passive"))
    )
    (net (code "87") (name "unconnected-(JP1-Pad25)") (class "Default")
      (node (ref "JP1") (pin "25") (pinfunction "25_25") (pintype "passive"))
    )
    (net (code "88") (name "unconnected-(JP1-Pad26)") (class "Default")
      (node (ref "JP1") (pin "26") (pinfunction "26_26") (pintype "passive"))
    )
    (net (code "89") (name "unconnected-(JP1-Pad27)") (class "Default")
      (node (ref "JP1") (pin "27") (pinfunction "27_27") (pintype "passive"))
    )
    (net (code "90") (name "unconnected-(JP1-Pad28)") (class "Default")
      (node (ref "JP1") (pin "28") (pinfunction "28_28") (pintype "passive"))
    )
    (net (code "91") (name "unconnected-(JP1-Pad29)") (class "Default")
      (node (ref "JP1") (pin "29") (pinfunction "29_29") (pintype "passive"))
    )
    (net (code "92") (name "unconnected-(JP1-Pad30)") (class "Default")
      (node (ref "JP1") (pin "30") (pinfunction "30_30") (pintype "passive"))
    )
    (net (code "93") (name "unconnected-(JP1-Pad31)") (class "Default")
      (node (ref "JP1") (pin "31") (pinfunction "31_31") (pintype "passive"))
    )
    (net (code "94") (name "unconnected-(JP1-Pad32)") (class "Default")
      (node (ref "JP1") (pin "32") (pinfunction "32_32") (pintype "passive"))
    )
    (net (code "95") (name "unconnected-(JP1-Pad33)") (class "Default")
      (node (ref "JP1") (pin "33") (pinfunction "33_33") (pintype "passive"))
    )
    (net (code "96") (name "unconnected-(JP1-Pad34)") (class "Default")
      (node (ref "JP1") (pin "34") (pinfunction "34_34") (pintype "passive"))
    )
    (net (code "97") (name "unconnected-(JP1-Pad35)") (class "Default")
      (node (ref "JP1") (pin "35") (pinfunction "35_35") (pintype "passive"))
    )
    (net (code "98") (name "unconnected-(JP1-Pad36)") (class "Default")
      (node (ref "JP1") (pin "36") (pinfunction "36_36") (pintype "passive"))
    )
    (net (code "99") (name "unconnected-(JP1-Pad37)") (class "Default")
      (node (ref "JP1") (pin "37") (pinfunction "37_37") (pintype "passive"))
    )
    (net (code "100") (name "unconnected-(JP1-Pad38)") (class "Default")
      (node (ref "JP1") (pin "38") (pinfunction "38_38") (pintype "passive"))
    )
    (net (code "101") (name "unconnected-(JP1-Pad39)") (class "Default")
      (node (ref "JP1") (pin "39") (pinfunction "39_39") (pintype "passive"))
    )
    (net (code "102") (name "unconnected-(JP1-Pad40)") (class "Default")
      (node (ref "JP1") (pin "40") (pinfunction "40_40") (pintype "passive"))
    )
    (net (code "103") (name "unconnected-(PCT2075-OS-Pad3)") (class "Default")
      (node (ref "PCT2075") (pin "3") (pinfunction "OS_3") (pintype "bidirectional"))
    )
    (net (code "104") (name "unconnected-(U$2-CSN-Pad5)") (class "Default")
      (node (ref "U$2") (pin "5") (pinfunction "CSN_5") (pintype "bidirectional"))
    )
    (net (code "105") (name "unconnected-(U$2-MISO-Pad10)") (class "Default")
      (node (ref "U$2") (pin "10") (pinfunction "MISO_10") (pintype "bidirectional"))
    )
    (net (code "106") (name "unconnected-(U$2-MOSI-Pad8)") (class "Default")
      (node (ref "U$2") (pin "8") (pinfunction "MOSI_8") (pintype "bidirectional"))
    )
    (net (code "107") (name "unconnected-(U$2-SCLK-Pad6)") (class "Default")
      (node (ref "U$2") (pin "6") (pinfunction "SCLK_6") (pintype "bidirectional"))
    )
    (net (code "108") (name "unconnected-(U$4-DNC-Pad3)") (class "Default")
      (node (ref "U$4") (pin "3") (pinfunction "DNC_3") (pintype "bidirectional"))
    )
    (net (code "109") (name "unconnected-(U$6-OTG-Pad4)") (class "Default")
      (node (ref "U$6") (pin "4") (pinfunction "OTG_4") (pintype "bidirectional"))
    )
  )
)
